# Compressor_and_Sidechain.net
KiCad netlist of a schematic drawn in Altium Designer
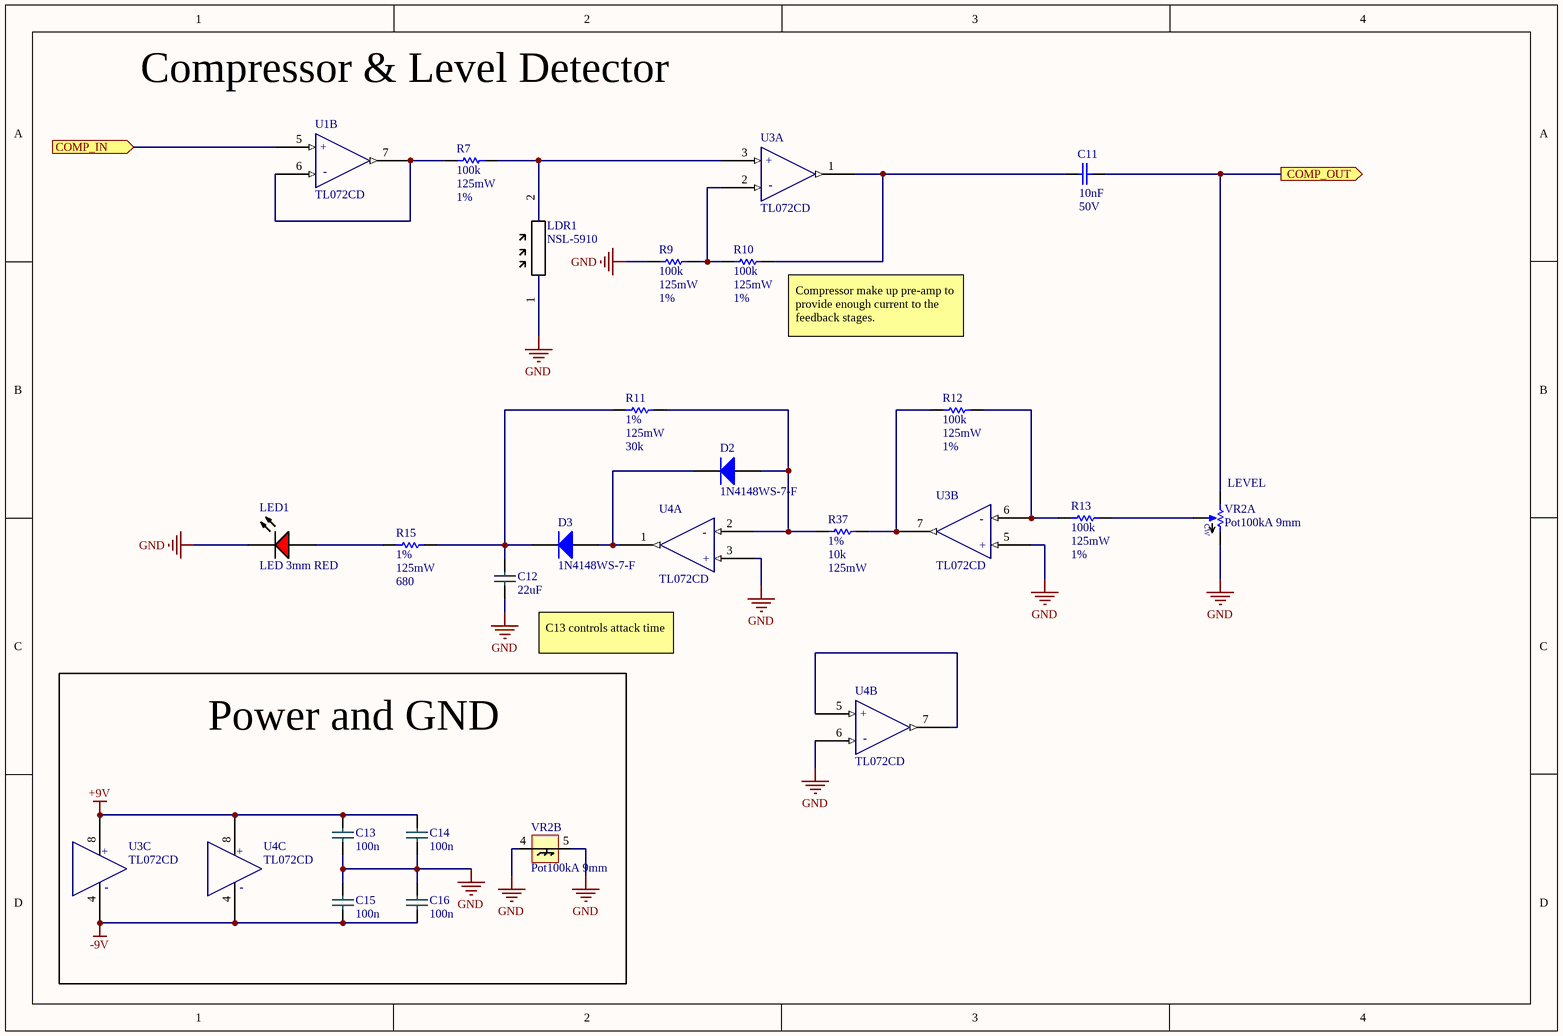
[diagram p0: Compressor and Sidechain.SchDoc]

(export (version "E")
  (design (tool "Eeschema 10.0.6"))
  (components
    (comp (ref "C11")
      (value "Cap 10nF 0805 C0G")
      (footprint "0805-CAP")
      (description "Cap 10nF 0805 C0G 50V +-5%")
      (fields (field (name "CAPACITANCE") "10nF") (field (name "RATED VOLTAGE") "50V"))
      (libsource (lib "Darkglass Electronics") (part "Capacitor Non-polarized"))
    )
    (comp (ref "C12")
      (value "22uF")
      (footprint "1206-CAP")
      (description "22uF, 25V, X5R, 20%")
      (fields (field (name "TOLERANCE") "20%") (field (name "Comment") "Cap 1206 22uF"))
      (libsource (lib "Darkglass Electronics") (part "Capacitor NP"))
    )
    (comp (ref "C13")
      (value "100n")
      (footprint "0805-CAP")
      (description "0.1uF 25volts C0G 5%")
      (fields
        (field (name "MOUSER PART") "81-GRM31C5C1E104JA01")
        (field (name "Comment") "Cap 0805 100nF 4")
        (field (name "PUBLISHER") "Altium Limited")
      )
      (libsource (lib "Darkglass Electronics") (part "Capacitor NP"))
    )
    (comp (ref "C14")
      (value "100n")
      (footprint "0805-CAP")
      (description "0.1uF 25volts C0G 5%")
      (fields
        (field (name "MOUSER PART") "81-GRM31C5C1E104JA01")
        (field (name "Comment") "Cap 0805 100nF 4")
        (field (name "PUBLISHER") "Altium Limited")
      )
      (libsource (lib "Darkglass Electronics") (part "Capacitor NP"))
    )
    (comp (ref "C15")
      (value "100n")
      (footprint "0805-CAP")
      (description "0.1uF 25volts C0G 5%")
      (fields
        (field (name "MOUSER PART") "81-GRM31C5C1E104JA01")
        (field (name "Comment") "Cap 0805 100nF 4")
        (field (name "PUBLISHER") "Altium Limited")
      )
      (libsource (lib "Darkglass Electronics") (part "Capacitor NP"))
    )
    (comp (ref "C16")
      (value "100n")
      (footprint "0805-CAP")
      (description "0.1uF 25volts C0G 5%")
      (fields
        (field (name "MOUSER PART") "81-GRM31C5C1E104JA01")
        (field (name "Comment") "Cap 0805 100nF 4")
        (field (name "PUBLISHER") "Altium Limited")
      )
      (libsource (lib "Darkglass Electronics") (part "Capacitor NP"))
    )
    (comp (ref "D2")
      (value "1N4148WS-7-F")
      (footprint "1N4148WS-7-F")
      (description "Fast Switching Diode, 75 V, 0.3 A, -65 to 150 degC, 2-Pin SOD323, RoHS, Tape and Reel")
      (fields
        (field (name "VOLTAGE") "75V")
        (field (name "MANUFACTURER") "Pericom")
        (field (name "AVAILABLE PREVIEW IMAGES") "2D")
      )
      (libsource (lib "Darkglass Electronics") (part "Symbol"))
    )
    (comp (ref "D3")
      (value "1N4148WS-7-F")
      (footprint "1N4148WS-7-F")
      (description "Fast Switching Diode, 75 V, 0.3 A, -65 to 150 degC, 2-Pin SOD323, RoHS, Tape and Reel")
      (fields
        (field (name "VOLTAGE") "75V")
        (field (name "MANUFACTURER") "Pericom")
        (field (name "AVAILABLE PREVIEW IMAGES") "2D")
      )
      (libsource (lib "Darkglass Electronics") (part "Symbol"))
    )
    (comp (ref "LDR1")
      (value "NSL-5910")
      (footprint "FB_28C0236-0JW-10:FB_28C0236-0JW-10")
      (description "Ambient Light Sensors Hermetic Photocell")
      (libsource (lib "Parts") (part "NSL-5910"))
    )
    (comp (ref "LED1")
      (value "LED 3mm RED")
      (footprint "KING-WP710A10QBCD_V")
      (description "THT LED round mono-color waterclear, WL-TMRW , RED")
      (fields
        (field (name "PARTNUMBER") "151034rs03000")
        (field (name "MANUFACTURER") "Wuerth Elektronik")
        (field (name "AVAILABLE PREVIEW IMAGES") "2D")
      )
      (libsource (lib "Darkglass Electronics") (part "LED 3mm RED"))
    )
    (comp (ref "R7")
      (value "Res 100k 1% 0805")
      (footprint "0805-RES")
      (description "Resistor 100k +-1% 0805 Thin film 0.125W +-50ppm/°C")
      (fields
        (field (name "RESISTANCE") "100k")
        (field (name "POWER") "125mW")
        (field (name "TOLERANCE (+-)") "1%")
      )
      (libsource (lib "Darkglass Electronics") (part "Resistor"))
    )
    (comp (ref "R9")
      (value "Res 100k 1% 0805")
      (footprint "0805-RES")
      (description "Resistor 100k +-1% 0805 Thin film 0.125W +-50ppm/°C")
      (fields
        (field (name "RESISTANCE") "100k")
        (field (name "POWER") "125mW")
        (field (name "TOLERANCE (+-)") "1%")
      )
      (libsource (lib "Darkglass Electronics") (part "Resistor"))
    )
    (comp (ref "R10")
      (value "Res 100k 1% 0805")
      (footprint "0805-RES")
      (description "Resistor 100k +-1% 0805 Thin film 0.125W +-50ppm/°C")
      (fields
        (field (name "RESISTANCE") "100k")
        (field (name "POWER") "125mW")
        (field (name "TOLERANCE (+-)") "1%")
      )
      (libsource (lib "Darkglass Electronics") (part "Resistor"))
    )
    (comp (ref "R11")
      (value "Res 30k 1% 0805")
      (footprint "0805-RES")
      (description "Resistor 30k +-1% 0805 Thin film 0.125W +-50ppm/°C")
      (fields
        (field (name "TOLERANCE (+-)") "1%")
        (field (name "POWER") "125mW")
        (field (name "RESISTANCE") "30k")
      )
      (libsource (lib "Darkglass Electronics") (part "Resistor"))
    )
    (comp (ref "R12")
      (value "Res 100k 1% 0805")
      (footprint "0805-RES")
      (description "Resistor 100k +-1% 0805 Thin film 0.125W +-50ppm/°C")
      (fields
        (field (name "RESISTANCE") "100k")
        (field (name "POWER") "125mW")
        (field (name "TOLERANCE (+-)") "1%")
      )
      (libsource (lib "Darkglass Electronics") (part "Resistor"))
    )
    (comp (ref "R13")
      (value "Res 100k 1% 0805")
      (footprint "0805-RES")
      (description "Resistor 100k +-1% 0805 Thin film 0.125W +-50ppm/°C")
      (fields
        (field (name "RESISTANCE") "100k")
        (field (name "POWER") "125mW")
        (field (name "TOLERANCE (+-)") "1%")
      )
      (libsource (lib "Darkglass Electronics") (part "Resistor"))
    )
    (comp (ref "R15")
      (value "Res 680R 1% 0805")
      (footprint "0805-RES")
      (description "Resistor 680R +-1% 0805 Thin film 0.125W +-50ppm/°C")
      (fields
        (field (name "TOLERANCE (+-)") "1%")
        (field (name "POWER") "125mW")
        (field (name "RESISTANCE") "680")
      )
      (libsource (lib "Darkglass Electronics") (part "Resistor"))
    )
    (comp (ref "R37")
      (value "Res 10k 1% 0805")
      (footprint "0805-RES")
      (description "Resistor 10k +-1% 0805 Thin film 0.125W +-50ppm/°C")
      (fields
        (field (name "TOLERANCE (+-)") "1%")
        (field (name "RESISTANCE") "10k")
        (field (name "POWER") "125mW")
      )
      (libsource (lib "Darkglass Electronics") (part "Resistor"))
    )
    (comp (ref "U1")
      (value "TL072CD")
      (footprint "SOIC8-127P600X175-8N")
      (description "Operational Amplifiers - Op Amps Dual Low Noise JFET SOIC8")
      (libsource (lib "Darkglass Electronics") (part "TL072CD"))
    )
    (comp (ref "U3")
      (value "TL072CD")
      (footprint "SOIC8-127P600X175-8N")
      (description "Operational Amplifiers - Op Amps Dual Low Noise JFET SOIC8")
      (libsource (lib "Darkglass Electronics") (part "TL072CD"))
    )
    (comp (ref "U4")
      (value "TL072CD")
      (footprint "SOIC8-127P600X175-8N")
      (description "Operational Amplifiers - Op Amps Dual Low Noise JFET SOIC8")
      (libsource (lib "Darkglass Electronics") (part "TL072CD"))
    )
    (comp (ref "VR2")
      (value "Pot100kA 9mm")
      (footprint "LJV 9mm pot")
      (description "LJV 9mm pot")
      (fields
        (field (name "DARKGLASS PART") "D00-0000")
        (field (name "MANUFACTURER PART NUMBER") "RP09110NOBA-H02-1484 (A104,KA15A6.5)")
      )
      (libsource (lib "Darkglass Electronics") (part "Pot100kA 9mm"))
    )
  )
  (nets
    (net (code "1") (name "+9V") (class "Default")
      (node (ref "C13") (pin "2") (pinfunction "2_2") (pintype "passive"))
      (node (ref "C14") (pin "2") (pinfunction "2_2") (pintype "passive"))
      (node (ref "U3") (pin "8") (pinfunction "V+_8") (pintype "power_in"))
      (node (ref "U4") (pin "8") (pinfunction "V+_8") (pintype "power_in"))
    )
    (net (code "2") (name "-9V") (class "Default")
      (node (ref "C15") (pin "1") (pinfunction "1_1") (pintype "passive"))
      (node (ref "C16") (pin "1") (pinfunction "1_1") (pintype "passive"))
      (node (ref "U3") (pin "4") (pinfunction "V-_4") (pintype "power_in"))
      (node (ref "U4") (pin "4") (pinfunction "V-_4") (pintype "power_in"))
    )
    (net (code "3") (name "/COMP_IN") (class "Default")
      (node (ref "U1") (pin "5") (pinfunction "IN+_5") (pintype "input"))
    )
    (net (code "4") (name "/COMP_OUT") (class "Default")
      (node (ref "C11") (pin "2") (pinfunction "2_2") (pintype "passive"))
      (node (ref "VR2") (pin "1") (pinfunction "CCWPIN_1") (pintype "passive"))
    )
    (net (code "5") (name "GND") (class "Default")
      (node (ref "C12") (pin "1") (pinfunction "1_1") (pintype "passive"))
      (node (ref "C13") (pin "1") (pinfunction "1_1") (pintype "passive"))
      (node (ref "C14") (pin "1") (pinfunction "1_1") (pintype "passive"))
      (node (ref "C15") (pin "2") (pinfunction "2_2") (pintype "passive"))
      (node (ref "C16") (pin "2") (pinfunction "2_2") (pintype "passive"))
      (node (ref "LDR1") (pin "1") (pinfunction "1_1") (pintype "passive"))
      (node (ref "LED1") (pin "2") (pinfunction "K_2") (pintype "passive"))
      (node (ref "R9") (pin "2") (pinfunction "2_2") (pintype "passive"))
      (node (ref "U3") (pin "5") (pinfunction "IN+_5") (pintype "input"))
      (node (ref "U4") (pin "3") (pinfunction "IN+_3") (pintype "input"))
      (node (ref "U4") (pin "6") (pinfunction "IN-_6") (pintype "input"))
      (node (ref "VR2") (pin "3") (pinfunction "CWPIN_3") (pintype "passive"))
      (node (ref "VR2") (pin "4") (pinfunction "4_4") (pintype "passive"))
      (node (ref "VR2") (pin "5") (pinfunction "5_5") (pintype "passive"))
    )
    (net (code "6") (name "Net-(D2-A)") (class "Default")
      (node (ref "D2") (pin "1") (pinfunction "A_1") (pintype "passive"))
      (node (ref "R11") (pin "2") (pinfunction "2_2") (pintype "passive"))
      (node (ref "R37") (pin "1") (pinfunction "1_1") (pintype "passive"))
      (node (ref "U4") (pin "2") (pinfunction "IN-_2") (pintype "input"))
    )
    (net (code "7") (name "Net-(D2-K)") (class "Default")
      (node (ref "D2") (pin "2") (pinfunction "K_2") (pintype "passive"))
      (node (ref "D3") (pin "1") (pinfunction "A_1") (pintype "passive"))
      (node (ref "U4") (pin "1") (pinfunction "OUT_1") (pintype "output"))
    )
    (net (code "8") (name "Net-(D3-K)") (class "Default")
      (node (ref "C12") (pin "2") (pinfunction "2_2") (pintype "passive"))
      (node (ref "D3") (pin "2") (pinfunction "K_2") (pintype "passive"))
      (node (ref "R11") (pin "1") (pinfunction "1_1") (pintype "passive"))
      (node (ref "R15") (pin "2") (pinfunction "2_2") (pintype "passive"))
    )
    (net (code "9") (name "Net-(LED1-A)") (class "Default")
      (node (ref "LED1") (pin "1") (pinfunction "A_1") (pintype "passive"))
      (node (ref "R15") (pin "1") (pinfunction "1_1") (pintype "passive"))
    )
    (net (code "10") (name "Net-(R12-Pad2)") (class "Default")
      (node (ref "R12") (pin "2") (pinfunction "2_2") (pintype "passive"))
      (node (ref "R37") (pin "2") (pinfunction "2_2") (pintype "passive"))
      (node (ref "U3") (pin "7") (pinfunction "7_7") (pintype "output"))
    )
    (net (code "11") (name "Net-(U1B-IN-)") (class "Default")
      (node (ref "R7") (pin "2") (pinfunction "2_2") (pintype "passive"))
      (node (ref "U1") (pin "6") (pinfunction "IN-_6") (pintype "input"))
      (node (ref "U1") (pin "7") (pinfunction "7_7") (pintype "output"))
    )
    (net (code "12") (name "Net-(U3A-IN+)") (class "Default")
      (node (ref "LDR1") (pin "2") (pinfunction "2_2") (pintype "passive"))
      (node (ref "R7") (pin "1") (pinfunction "1_1") (pintype "passive"))
      (node (ref "U3") (pin "3") (pinfunction "IN+_3") (pintype "input"))
    )
    (net (code "13") (name "Net-(U3A-IN-)") (class "Default")
      (node (ref "R10") (pin "2") (pinfunction "2_2") (pintype "passive"))
      (node (ref "R9") (pin "1") (pinfunction "1_1") (pintype "passive"))
      (node (ref "U3") (pin "2") (pinfunction "IN-_2") (pintype "input"))
    )
    (net (code "14") (name "Net-(U3A-OUT)") (class "Default")
      (node (ref "C11") (pin "1") (pinfunction "1_1") (pintype "passive"))
      (node (ref "R10") (pin "1") (pinfunction "1_1") (pintype "passive"))
      (node (ref "U3") (pin "1") (pinfunction "OUT_1") (pintype "output"))
    )
    (net (code "15") (name "Net-(U3B-IN-)") (class "Default")
      (node (ref "R12") (pin "1") (pinfunction "1_1") (pintype "passive"))
      (node (ref "R13") (pin "2") (pinfunction "2_2") (pintype "passive"))
      (node (ref "U3") (pin "6") (pinfunction "IN-_6") (pintype "input"))
    )
    (net (code "16") (name "Net-(U4B-IN+)") (class "Default")
      (node (ref "U4") (pin "5") (pinfunction "IN+_5") (pintype "input"))
      (node (ref "U4") (pin "7") (pinfunction "7_7") (pintype "output"))
    )
    (net (code "17") (name "Net-(VR2A-WIPER)") (class "Default")
      (node (ref "R13") (pin "1") (pinfunction "1_1") (pintype "passive"))
      (node (ref "VR2") (pin "2") (pinfunction "WIPER_2") (pintype "passive"))
    )
  )
)
